# Intan_RHS2116.net
KiCad netlist of a schematic drawn in Altium Designer
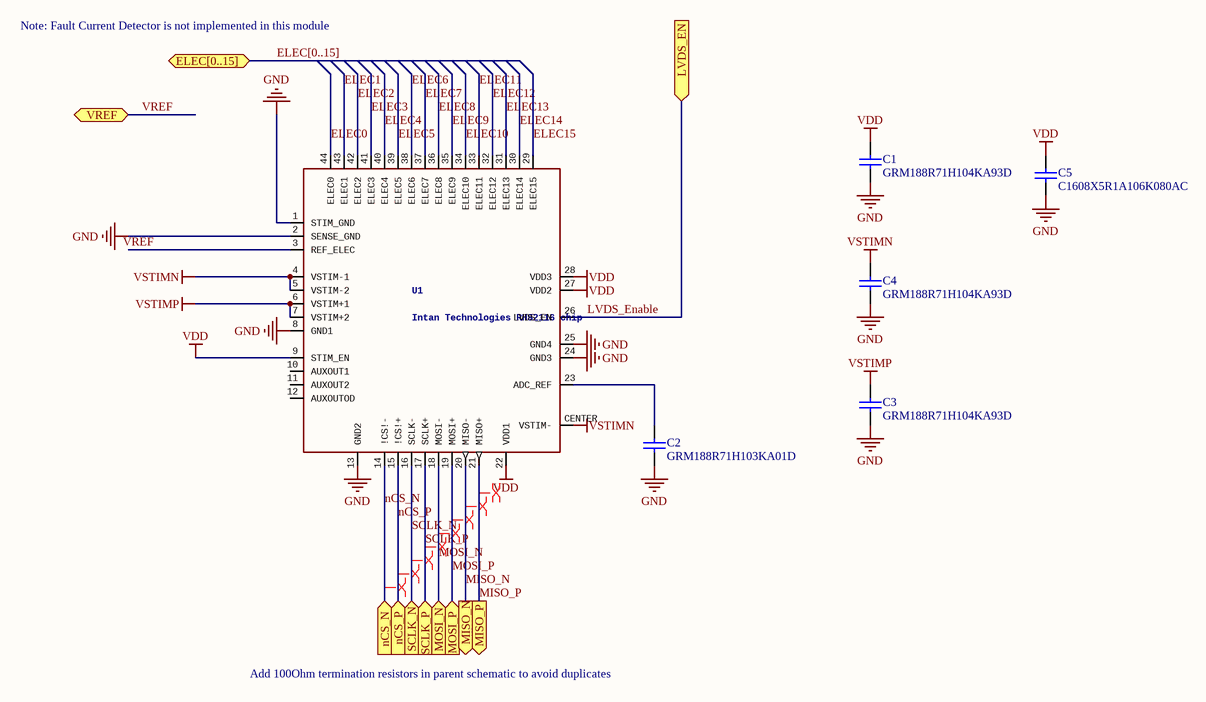
[diagram p0: Intan_RHS2116.SchDoc]

(export (version "E")
  (design (tool "Eeschema 10.0.6"))
  (components
    (comp (ref "C1")
      (value "GRM188R71H104KA93D")
      (footprint "CAPC1608X90X35ML10T15")
      (description "Chip Capacitor, 0.1 uF, +/- 10%, 50 V, -55 to 125 degC, 0603 (1608 Metric), RoHS, Tape and Reel")
      (fields (field (name "TOLERANCE") "10%") (field (name "VOLTAGE") "50V"))
      (libsource (lib "Altium Content Vault") (part "CAP-NP-2"))
    )
    (comp (ref "C2")
      (value "GRM188R71H103KA01D")
      (footprint "CAPC1608X90X35ML10T15")
      (description "Chip Capacitor, 10 nF, +/- 10%, 50 V, -55 to 125 degC, 0603 (1608 Metric), RoHS, Tape and Reel")
      (fields (field (name "VOLTAGE") "50V") (field (name "TOLERANCE") "10%"))
      (libsource (lib "Altium Content Vault") (part "CAP-NP-2"))
    )
    (comp (ref "C3")
      (value "GRM188R71H104KA93D")
      (footprint "CAPC1608X90X35ML10T15")
      (description "Chip Capacitor, 0.1 uF, +/- 10%, 50 V, -55 to 125 degC, 0603 (1608 Metric), RoHS, Tape and Reel")
      (fields (field (name "TOLERANCE") "10%") (field (name "VOLTAGE") "50V"))
      (libsource (lib "Altium Content Vault") (part "CAP-NP-2"))
    )
    (comp (ref "C4")
      (value "GRM188R71H104KA93D")
      (footprint "CAPC1608X90X35ML10T15")
      (description "Chip Capacitor, 0.1 uF, +/- 10%, 50 V, -55 to 125 degC, 0603 (1608 Metric), RoHS, Tape and Reel")
      (fields (field (name "TOLERANCE") "10%") (field (name "VOLTAGE") "50V"))
      (libsource (lib "Altium Content Vault") (part "CAP-NP-2"))
    )
    (comp (ref "C5")
      (value "C1608X5R1A106K080AC")
      (footprint "CAPC1608X90X20ML10")
      (description "Chip Capacitor, 10 uF, +/- 10%, 10 V, -55 to 85 degC, 0603 (1608 Metric), RoHS, Tape and Reel")
      (fields
        (field (name "PCN PART NUMBER") "MLCCPartNumberChange30/Nov/2012")
        (field (name "TOLERANCE") "±10%")
      )
      (libsource (lib "Altium Content Vault") (part "CAP-NP-2"))
    )
    (comp (ref "U1")
      (value "Intan Technologies RHS2116 chip")
      (footprint "intan_rhs2116:QFN44_7_X_7")
      (fields
        (field (name "MANUFACTURER") "Intan Technologies")
        (field (name "MANUFACTURER PART NUMBER") "RHS2116")
      )
      (libsource (lib "intan_rhs2116") (part "RHS2116_QFN"))
    )
  )
  (nets
    (net (code "1") (name "/ELEC0") (class "Default")
      (node (ref "U1") (pin "44") (pinfunction "ELEC0_44") (pintype "passive"))
    )
    (net (code "2") (name "/ELEC1") (class "Default")
      (node (ref "U1") (pin "43") (pinfunction "ELEC1_43") (pintype "passive"))
    )
    (net (code "3") (name "/ELEC2") (class "Default")
      (node (ref "U1") (pin "42") (pinfunction "ELEC2_42") (pintype "passive"))
    )
    (net (code "4") (name "/ELEC3") (class "Default")
      (node (ref "U1") (pin "41") (pinfunction "ELEC3_41") (pintype "passive"))
    )
    (net (code "5") (name "/ELEC4") (class "Default")
      (node (ref "U1") (pin "40") (pinfunction "ELEC4_40") (pintype "passive"))
    )
    (net (code "6") (name "/ELEC5") (class "Default")
      (node (ref "U1") (pin "39") (pinfunction "ELEC5_39") (pintype "passive"))
    )
    (net (code "7") (name "/ELEC6") (class "Default")
      (node (ref "U1") (pin "38") (pinfunction "ELEC6_38") (pintype "passive"))
    )
    (net (code "8") (name "/ELEC7") (class "Default")
      (node (ref "U1") (pin "37") (pinfunction "ELEC7_37") (pintype "passive"))
    )
    (net (code "9") (name "/ELEC8") (class "Default")
      (node (ref "U1") (pin "36") (pinfunction "ELEC8_36") (pintype "passive"))
    )
    (net (code "10") (name "/ELEC9") (class "Default")
      (node (ref "U1") (pin "35") (pinfunction "ELEC9_35") (pintype "passive"))
    )
    (net (code "11") (name "/ELEC10") (class "Default")
      (node (ref "U1") (pin "34") (pinfunction "ELEC10_34") (pintype "passive"))
    )
    (net (code "12") (name "/ELEC11") (class "Default")
      (node (ref "U1") (pin "33") (pinfunction "ELEC11_33") (pintype "passive"))
    )
    (net (code "13") (name "/ELEC12") (class "Default")
      (node (ref "U1") (pin "32") (pinfunction "ELEC12_32") (pintype "passive"))
    )
    (net (code "14") (name "/ELEC13") (class "Default")
      (node (ref "U1") (pin "31") (pinfunction "ELEC13_31") (pintype "passive"))
    )
    (net (code "15") (name "/ELEC14") (class "Default")
      (node (ref "U1") (pin "30") (pinfunction "ELEC14_30") (pintype "passive"))
    )
    (net (code "16") (name "/ELEC15") (class "Default")
      (node (ref "U1") (pin "29") (pinfunction "ELEC15_29") (pintype "passive"))
    )
    (net (code "18") (name "/LVDS_Enable") (class "Default")
      (node (ref "U1") (pin "26") (pinfunction "LVDS_EN_26") (pintype "passive"))
    )
    (net (code "19") (name "/MISO_N") (class "Default")
      (node (ref "U1") (pin "20") (pinfunction "MISO-_20") (pintype "output"))
    )
    (net (code "20") (name "/MISO_P") (class "Default")
      (node (ref "U1") (pin "21") (pinfunction "MISO+_21") (pintype "output"))
    )
    (net (code "21") (name "/MOSI_N") (class "Default")
      (node (ref "U1") (pin "18") (pinfunction "MOSI-_18") (pintype "passive"))
    )
    (net (code "22") (name "/MOSI_P") (class "Default")
      (node (ref "U1") (pin "19") (pinfunction "MOSI+_19") (pintype "passive"))
    )
    (net (code "23") (name "/SCLK_N") (class "Default")
      (node (ref "U1") (pin "16") (pinfunction "SCLK-_16") (pintype "passive"))
    )
    (net (code "24") (name "/SCLK_P") (class "Default")
      (node (ref "U1") (pin "17") (pinfunction "SCLK+_17") (pintype "passive"))
    )
    (net (code "25") (name "/VREF") (class "Default")
      (node (ref "U1") (pin "3") (pinfunction "REF_ELEC_3") (pintype "passive"))
    )
    (net (code "26") (name "/nCS_N") (class "Default")
      (node (ref "U1") (pin "14") (pinfunction "!CS!-_14") (pintype "passive"))
    )
    (net (code "27") (name "/nCS_P") (class "Default")
      (node (ref "U1") (pin "15") (pinfunction "!CS!+_15") (pintype "passive"))
    )
    (net (code "28") (name "GND") (class "Default")
      (node (ref "C1") (pin "1") (pinfunction "1_1") (pintype "passive"))
      (node (ref "C2") (pin "1") (pinfunction "1_1") (pintype "passive"))
      (node (ref "C3") (pin "1") (pinfunction "1_1") (pintype "passive"))
      (node (ref "C4") (pin "1") (pinfunction "1_1") (pintype "passive"))
      (node (ref "C5") (pin "1") (pinfunction "1_1") (pintype "passive"))
      (node (ref "U1") (pin "1") (pinfunction "STIM_GND_1") (pintype "power_in"))
      (node (ref "U1") (pin "13") (pinfunction "GND2_13") (pintype "power_in"))
      (node (ref "U1") (pin "2") (pinfunction "SENSE_GND_2") (pintype "power_in"))
      (node (ref "U1") (pin "24") (pinfunction "GND3_24") (pintype "power_in"))
      (node (ref "U1") (pin "25") (pinfunction "GND4_25") (pintype "power_in"))
      (node (ref "U1") (pin "8") (pinfunction "GND1_8") (pintype "power_in"))
    )
    (net (code "29") (name "Net-(U1-ADC_REF)") (class "Default")
      (node (ref "C2") (pin "2") (pinfunction "2_2") (pintype "passive"))
      (node (ref "U1") (pin "23") (pinfunction "ADC_REF_23") (pintype "passive"))
    )
    (net (code "30") (name "VDD") (class "Default")
      (node (ref "C1") (pin "2") (pinfunction "2_2") (pintype "passive"))
      (node (ref "C5") (pin "2") (pinfunction "2_2") (pintype "passive"))
      (node (ref "U1") (pin "22") (pinfunction "VDD1_22") (pintype "power_in"))
      (node (ref "U1") (pin "27") (pinfunction "VDD2_27") (pintype "power_in"))
      (node (ref "U1") (pin "28") (pinfunction "VDD3_28") (pintype "power_in"))
      (node (ref "U1") (pin "9") (pinfunction "STIM_EN_9") (pintype "passive"))
    )
    (net (code "31") (name "VSTIMN") (class "Default")
      (node (ref "C4") (pin "2") (pinfunction "2_2") (pintype "passive"))
      (node (ref "U1") (pin "4") (pinfunction "VSTIM-1_4") (pintype "power_in"))
      (node (ref "U1") (pin "5") (pinfunction "VSTIM-2_5") (pintype "power_in"))
      (node (ref "U1") (pin "CENTER") (pinfunction "VSTIM-_CENTER") (pintype "power_in"))
    )
    (net (code "32") (name "VSTIMP") (class "Default")
      (node (ref "C3") (pin "2") (pinfunction "2_2") (pintype "passive"))
      (node (ref "U1") (pin "6") (pinfunction "VSTIM+1_6") (pintype "power_in"))
      (node (ref "U1") (pin "7") (pinfunction "VSTIM+2_7") (pintype "power_in"))
    )
    (net (code "33") (name "unconnected-(U1-AUXOUT1-Pad10)") (class "Default")
      (node (ref "U1") (pin "10") (pinfunction "AUXOUT1_10") (pintype "tri_state"))
    )
    (net (code "34") (name "unconnected-(U1-AUXOUT2-Pad11)") (class "Default")
      (node (ref "U1") (pin "11") (pinfunction "AUXOUT2_11") (pintype "tri_state"))
    )
    (net (code "35") (name "unconnected-(U1-AUXOUTOD-Pad12)") (class "Default")
      (node (ref "U1") (pin "12") (pinfunction "AUXOUTOD_12") (pintype "open_collector"))
    )
  )
)
